# FPGA_B.net
KiCad netlist of a schematic drawn in Altium Designer
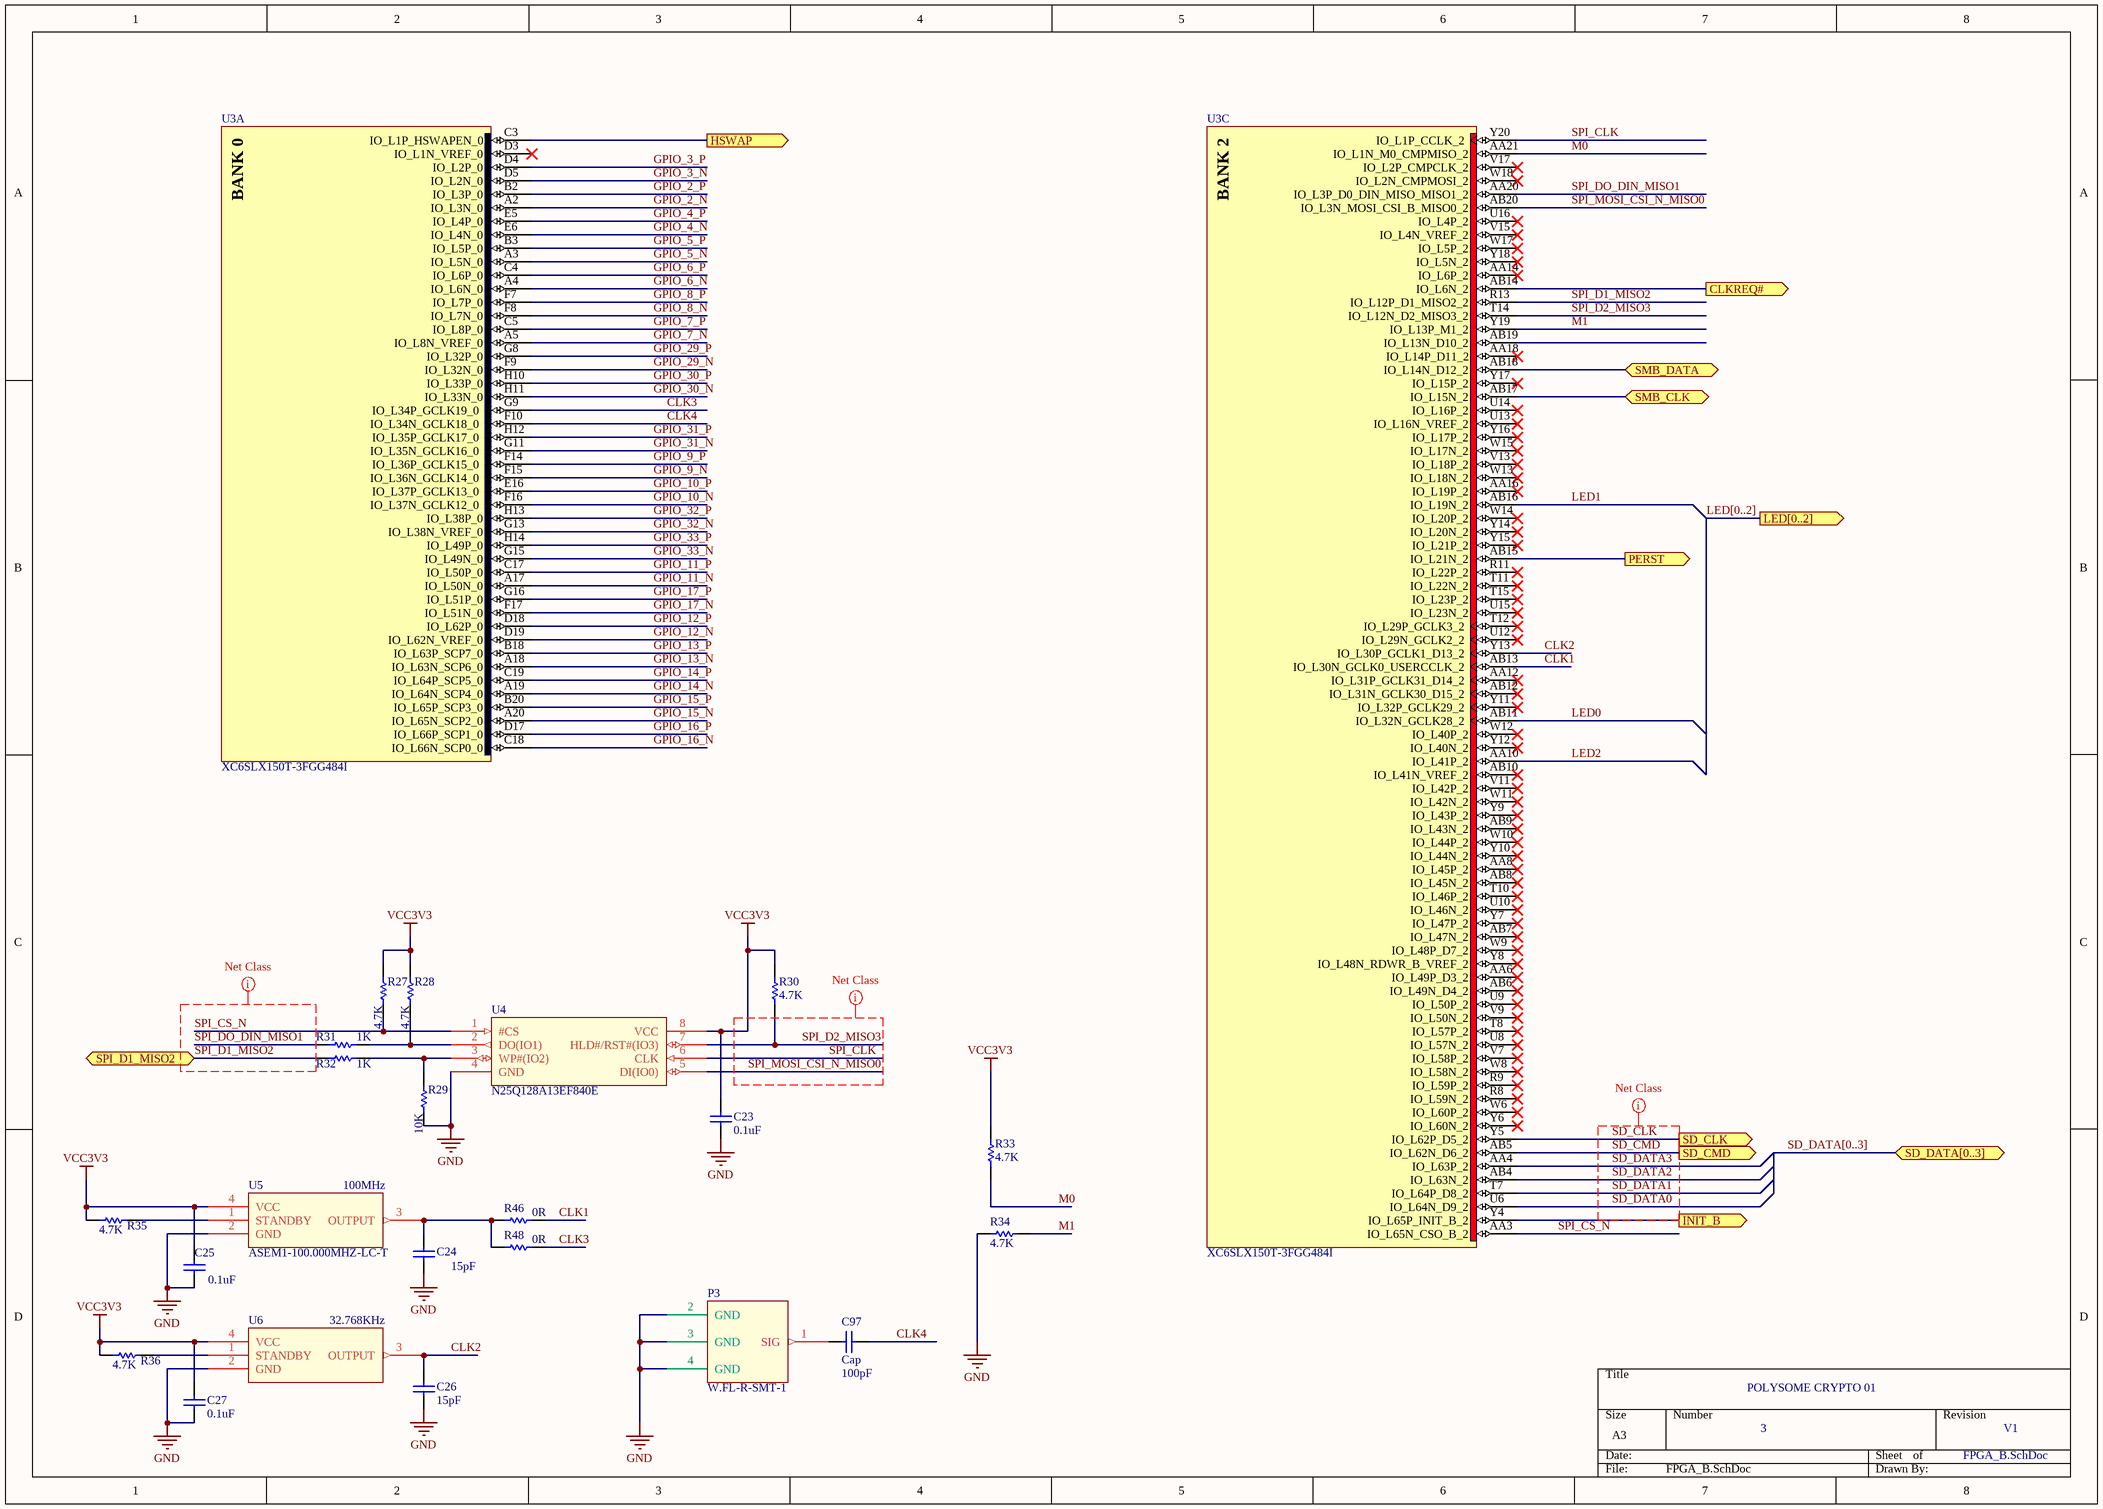
[diagram p0: FPGA_B.SchDoc]

(export (version "E")
  (design (tool "Eeschema 10.0.6"))
  (components
    (comp (ref "C23")
      (value "0.1uF")
      (footprint "0402")
      (description "Capacitor (Semiconductor SIM Model)")
      (fields (field (name "Comment") "Cap Semi") (field (name "PUBLISHER") "Altium Limited"))
      (libsource (lib "Miscellaneous Devices") (part "Cap Semi"))
    )
    (comp (ref "C24")
      (value "15pF")
      (footprint "0402")
      (description "Capacitor (Semiconductor SIM Model)")
      (fields (field (name "Comment") "Cap Semi") (field (name "PUBLISHER") "Altium Limited"))
      (libsource (lib "Miscellaneous Devices") (part "Cap Semi"))
    )
    (comp (ref "C25")
      (value "0.1uF")
      (footprint "0402")
      (description "Capacitor (Semiconductor SIM Model)")
      (fields (field (name "Comment") "Cap Semi") (field (name "PUBLISHER") "Altium Limited"))
      (libsource (lib "Miscellaneous Devices") (part "Cap Semi"))
    )
    (comp (ref "C26")
      (value "15pF")
      (footprint "0402")
      (description "Capacitor (Semiconductor SIM Model)")
      (fields (field (name "Comment") "Cap Semi") (field (name "PUBLISHER") "Altium Limited"))
      (libsource (lib "Miscellaneous Devices") (part "Cap Semi"))
    )
    (comp (ref "C27")
      (value "0.1uF")
      (footprint "0402")
      (description "Capacitor (Semiconductor SIM Model)")
      (fields (field (name "Comment") "Cap Semi") (field (name "PUBLISHER") "Altium Limited"))
      (libsource (lib "Miscellaneous Devices") (part "Cap Semi"))
    )
    (comp (ref "C97")
      (value "Cap")
      (footprint "0402")
      (description "Capacitor")
      (fields (field (name "ALTIUM_VALUE") "100pF") (field (name "PUBLISHER") "Altium Limited"))
      (libsource (lib "Miscellaneous Devices") (part "Cap"))
    )
    (comp (ref "P3")
      (value "W.FL-R-SMT-1")
      (footprint "W.FL-R-SMT-1")
      (libsource (lib "PolySomeCrypto01") (part "W.FL-R-SMT-1"))
    )
    (comp (ref "R27")
      (value "4.7K")
      (footprint "0402")
      (description "Semiconductor Resistor")
      (fields (field (name "Comment") "Res Semi") (field (name "PUBLISHER") "Altium Limited"))
      (libsource (lib "Miscellaneous Devices") (part "Res Semi"))
    )
    (comp (ref "R28")
      (value "4.7K")
      (footprint "0402")
      (description "Semiconductor Resistor")
      (fields (field (name "Comment") "Res Semi") (field (name "PUBLISHER") "Altium Limited"))
      (libsource (lib "Miscellaneous Devices") (part "Res Semi"))
    )
    (comp (ref "R29")
      (value "10K")
      (footprint "0402")
      (description "Semiconductor Resistor")
      (fields (field (name "Comment") "Res Semi") (field (name "PUBLISHER") "Altium Limited"))
      (libsource (lib "Miscellaneous Devices") (part "Res Semi"))
    )
    (comp (ref "R30")
      (value "4.7K")
      (footprint "0402")
      (description "Semiconductor Resistor")
      (fields (field (name "Comment") "Res Semi") (field (name "PUBLISHER") "Altium Limited"))
      (libsource (lib "Miscellaneous Devices") (part "Res Semi"))
    )
    (comp (ref "R31")
      (value "1K")
      (footprint "0402")
      (description "Semiconductor Resistor")
      (fields (field (name "Comment") "Res Semi") (field (name "PUBLISHER") "Altium Limited"))
      (libsource (lib "Miscellaneous Devices") (part "Res Semi"))
    )
    (comp (ref "R32")
      (value "1K")
      (footprint "0402")
      (description "Semiconductor Resistor")
      (fields (field (name "Comment") "Res Semi") (field (name "PUBLISHER") "Altium Limited"))
      (libsource (lib "Miscellaneous Devices") (part "Res Semi"))
    )
    (comp (ref "R33")
      (value "4.7K")
      (footprint "0402")
      (description "Semiconductor Resistor")
      (fields (field (name "Comment") "Res Semi") (field (name "PUBLISHER") "Altium Limited"))
      (libsource (lib "Miscellaneous Devices") (part "Res Semi"))
    )
    (comp (ref "R34")
      (value "4.7K")
      (footprint "0402")
      (description "Semiconductor Resistor")
      (fields (field (name "Comment") "Res Semi") (field (name "PUBLISHER") "Altium Limited"))
      (libsource (lib "Miscellaneous Devices") (part "Res Semi"))
    )
    (comp (ref "R35")
      (value "4.7K")
      (footprint "0402")
      (description "Semiconductor Resistor")
      (fields (field (name "Comment") "Res Semi") (field (name "PUBLISHER") "Altium Limited"))
      (libsource (lib "Miscellaneous Devices") (part "Res Semi"))
    )
    (comp (ref "R36")
      (value "4.7K")
      (footprint "0402")
      (description "Semiconductor Resistor")
      (fields (field (name "Comment") "Res Semi") (field (name "PUBLISHER") "Altium Limited"))
      (libsource (lib "Miscellaneous Devices") (part "Res Semi"))
    )
    (comp (ref "R46")
      (value "0R")
      (footprint "0402")
      (description "Semiconductor Resistor")
      (fields (field (name "Comment") "Res Semi") (field (name "PUBLISHER") "Altium Limited"))
      (libsource (lib "Miscellaneous Devices") (part "Res Semi"))
    )
    (comp (ref "R48")
      (value "0R")
      (footprint "0402")
      (description "Semiconductor Resistor")
      (fields (field (name "Comment") "Res Semi") (field (name "PUBLISHER") "Altium Limited"))
      (libsource (lib "Miscellaneous Devices") (part "Res Semi"))
    )
    (comp (ref "U3")
      (value "XC6SLX150T-3FGG484I")
      (footprint "FGG484")
      (fields (field (name "PUBLISHER") "Altium Limited"))
      (libsource (lib "Xilinx Spartan-6") (part "XC6SLX150T-3FGG484I"))
    )
    (comp (ref "U4")
      (value "N25Q128A13EF840E")
      (footprint "8S2_L")
      (description "IC FLASH 128MBIT 108MHZ 8VDFN")
      (fields (field (name "MANUFACTURER") "Micron Technology Inc"))
      (libsource (lib "PolySomeCrypto01") (part "N25Q128A13EF840E"))
    )
    (comp (ref "U5")
      (value "ASEM1-100.000MHZ-LC-T")
      (footprint "DFN170P200X100-4N")
      (description "ABRACON - ASEM1-100.000MHZ-LC-T - MEMS OSC, 100MHZ, 3.2 X 2.5MM, CMOS")
      (fields (field (name "MANUFACTURER") "ABRACON"))
      (libsource (lib "PolySomeCrypto01") (part "ASEM1-100.000MHZ-LC-T"))
    )
    (comp (ref "U6")
      (value "ASEM1-LC-T")
      (description "ABRACON - ASEM1-HZ-LC-T - MEMS OSC, 3.2 X 2.5MM, CMOS")
      (fields
        (field (name "MANUFACTURER") "ABRACON")
        (field (name "MANUFACTURER PART NUMBER") "ASEM1-xxxxMHZ-LC-T")
      )
      (libsource (lib "PolySomeCrypto01") (part "ASEM1-HZ-LC-T"))
    )
  )
  (nets
    (net (code "1") (name "/CLK1") (class "Default")
      (node (ref "R46") (pin "2") (pinfunction "2_2") (pintype "passive"))
      (node (ref "U3") (pin "AB13") (pinfunction "IO_L30N_GCLK0_USERCCLK_2_AB13") (pintype "bidirectional"))
    )
    (net (code "2") (name "/CLK2") (class "Default")
      (node (ref "C26") (pin "1") (pinfunction "1_1") (pintype "passive"))
      (node (ref "U3") (pin "Y13") (pinfunction "IO_L30P_GCLK1_D13_2_Y13") (pintype "bidirectional"))
      (node (ref "U6") (pin "3") (pinfunction "OUTPUT_3") (pintype "output"))
    )
    (net (code "3") (name "/CLK3") (class "Default")
      (node (ref "R48") (pin "2") (pinfunction "2_2") (pintype "passive"))
      (node (ref "U3") (pin "G9") (pinfunction "IO_L34P_GCLK19_0_G9") (pintype "bidirectional"))
    )
    (net (code "4") (name "/CLK4") (class "Default")
      (node (ref "C97") (pin "2") (pinfunction "2_2") (pintype "passive"))
      (node (ref "U3") (pin "F10") (pinfunction "IO_L34N_GCLK18_0_F10") (pintype "bidirectional"))
    )
    (net (code "5") (name "/CLKREQ#") (class "Default")
      (node (ref "U3") (pin "AB14") (pinfunction "IO_L6N_2_AB14") (pintype "bidirectional"))
    )
    (net (code "6") (name "/GPIO_2_N") (class "Default")
      (node (ref "U3") (pin "A2") (pinfunction "IO_L3N_0_A2") (pintype "bidirectional"))
    )
    (net (code "7") (name "/GPIO_2_P") (class "Default")
      (node (ref "U3") (pin "B2") (pinfunction "IO_L3P_0_B2") (pintype "bidirectional"))
    )
    (net (code "8") (name "/GPIO_3_N") (class "Default")
      (node (ref "U3") (pin "D5") (pinfunction "IO_L2N_0_D5") (pintype "bidirectional"))
    )
    (net (code "9") (name "/GPIO_3_P") (class "Default")
      (node (ref "U3") (pin "D4") (pinfunction "IO_L2P_0_D4") (pintype "bidirectional"))
    )
    (net (code "10") (name "/GPIO_4_N") (class "Default")
      (node (ref "U3") (pin "E6") (pinfunction "IO_L4N_0_E6") (pintype "bidirectional"))
    )
    (net (code "11") (name "/GPIO_4_P") (class "Default")
      (node (ref "U3") (pin "E5") (pinfunction "IO_L4P_0_E5") (pintype "bidirectional"))
    )
    (net (code "12") (name "/GPIO_5_N") (class "Default")
      (node (ref "U3") (pin "A3") (pinfunction "IO_L5N_0_A3") (pintype "bidirectional"))
    )
    (net (code "13") (name "/GPIO_5_P") (class "Default")
      (node (ref "U3") (pin "B3") (pinfunction "IO_L5P_0_B3") (pintype "bidirectional"))
    )
    (net (code "14") (name "/GPIO_6_N") (class "Default")
      (node (ref "U3") (pin "A4") (pinfunction "IO_L6N_0_A4") (pintype "bidirectional"))
    )
    (net (code "15") (name "/GPIO_6_P") (class "Default")
      (node (ref "U3") (pin "C4") (pinfunction "IO_L6P_0_C4") (pintype "bidirectional"))
    )
    (net (code "16") (name "/GPIO_7_N") (class "Default")
      (node (ref "U3") (pin "A5") (pinfunction "IO_L8N_VREF_0_A5") (pintype "bidirectional"))
    )
    (net (code "17") (name "/GPIO_7_P") (class "Default")
      (node (ref "U3") (pin "C5") (pinfunction "IO_L8P_0_C5") (pintype "bidirectional"))
    )
    (net (code "18") (name "/GPIO_8_N") (class "Default")
      (node (ref "U3") (pin "F8") (pinfunction "IO_L7N_0_F8") (pintype "bidirectional"))
    )
    (net (code "19") (name "/GPIO_8_P") (class "Default")
      (node (ref "U3") (pin "F7") (pinfunction "IO_L7P_0_F7") (pintype "bidirectional"))
    )
    (net (code "20") (name "/GPIO_9_N") (class "Default")
      (node (ref "U3") (pin "F15") (pinfunction "IO_L36N_GCLK14_0_F15") (pintype "bidirectional"))
    )
    (net (code "21") (name "/GPIO_9_P") (class "Default")
      (node (ref "U3") (pin "F14") (pinfunction "IO_L36P_GCLK15_0_F14") (pintype "bidirectional"))
    )
    (net (code "22") (name "/GPIO_10_N") (class "Default")
      (node (ref "U3") (pin "F16") (pinfunction "IO_L37N_GCLK12_0_F16") (pintype "bidirectional"))
    )
    (net (code "23") (name "/GPIO_10_P") (class "Default")
      (node (ref "U3") (pin "E16") (pinfunction "IO_L37P_GCLK13_0_E16") (pintype "bidirectional"))
    )
    (net (code "24") (name "/GPIO_11_N") (class "Default")
      (node (ref "U3") (pin "A17") (pinfunction "IO_L50N_0_A17") (pintype "bidirectional"))
    )
    (net (code "25") (name "/GPIO_11_P") (class "Default")
      (node (ref "U3") (pin "C17") (pinfunction "IO_L50P_0_C17") (pintype "bidirectional"))
    )
    (net (code "26") (name "/GPIO_12_N") (class "Default")
      (node (ref "U3") (pin "D19") (pinfunction "IO_L62N_VREF_0_D19") (pintype "bidirectional"))
    )
    (net (code "27") (name "/GPIO_12_P") (class "Default")
      (node (ref "U3") (pin "D18") (pinfunction "IO_L62P_0_D18") (pintype "bidirectional"))
    )
    (net (code "28") (name "/GPIO_13_N") (class "Default")
      (node (ref "U3") (pin "A18") (pinfunction "IO_L63N_SCP6_0_A18") (pintype "bidirectional"))
    )
    (net (code "29") (name "/GPIO_13_P") (class "Default")
      (node (ref "U3") (pin "B18") (pinfunction "IO_L63P_SCP7_0_B18") (pintype "bidirectional"))
    )
    (net (code "30") (name "/GPIO_14_N") (class "Default")
      (node (ref "U3") (pin "A19") (pinfunction "IO_L64N_SCP4_0_A19") (pintype "bidirectional"))
    )
    (net (code "31") (name "/GPIO_14_P") (class "Default")
      (node (ref "U3") (pin "C19") (pinfunction "IO_L64P_SCP5_0_C19") (pintype "bidirectional"))
    )
    (net (code "32") (name "/GPIO_15_N") (class "Default")
      (node (ref "U3") (pin "A20") (pinfunction "IO_L65N_SCP2_0_A20") (pintype "bidirectional"))
    )
    (net (code "33") (name "/GPIO_15_P") (class "Default")
      (node (ref "U3") (pin "B20") (pinfunction "IO_L65P_SCP3_0_B20") (pintype "bidirectional"))
    )
    (net (code "34") (name "/GPIO_16_N") (class "Default")
      (node (ref "U3") (pin "C18") (pinfunction "IO_L66N_SCP0_0_C18") (pintype "bidirectional"))
    )
    (net (code "35") (name "/GPIO_16_P") (class "Default")
      (node (ref "U3") (pin "D17") (pinfunction "IO_L66P_SCP1_0_D17") (pintype "bidirectional"))
    )
    (net (code "36") (name "/GPIO_17_N") (class "Default")
      (node (ref "U3") (pin "F17") (pinfunction "IO_L51N_0_F17") (pintype "bidirectional"))
    )
    (net (code "37") (name "/GPIO_17_P") (class "Default")
      (node (ref "U3") (pin "G16") (pinfunction "IO_L51P_0_G16") (pintype "bidirectional"))
    )
    (net (code "38") (name "/GPIO_29_N") (class "Default")
      (node (ref "U3") (pin "F9") (pinfunction "IO_L32N_0_F9") (pintype "bidirectional"))
    )
    (net (code "39") (name "/GPIO_29_P") (class "Default")
      (node (ref "U3") (pin "G8") (pinfunction "IO_L32P_0_G8") (pintype "bidirectional"))
    )
    (net (code "40") (name "/GPIO_30_N") (class "Default")
      (node (ref "U3") (pin "H11") (pinfunction "IO_L33N_0_H11") (pintype "bidirectional"))
    )
    (net (code "41") (name "/GPIO_30_P") (class "Default")
      (node (ref "U3") (pin "H10") (pinfunction "IO_L33P_0_H10") (pintype "bidirectional"))
    )
    (net (code "42") (name "/GPIO_31_N") (class "Default")
      (node (ref "U3") (pin "G11") (pinfunction "IO_L35N_GCLK16_0_G11") (pintype "bidirectional"))
    )
    (net (code "43") (name "/GPIO_31_P") (class "Default")
      (node (ref "U3") (pin "H12") (pinfunction "IO_L35P_GCLK17_0_H12") (pintype "bidirectional"))
    )
    (net (code "44") (name "/GPIO_32_N") (class "Default")
      (node (ref "U3") (pin "G13") (pinfunction "IO_L38N_VREF_0_G13") (pintype "bidirectional"))
    )
    (net (code "45") (name "/GPIO_32_P") (class "Default")
      (node (ref "U3") (pin "H13") (pinfunction "IO_L38P_0_H13") (pintype "bidirectional"))
    )
    (net (code "46") (name "/GPIO_33_N") (class "Default")
      (node (ref "U3") (pin "G15") (pinfunction "IO_L49N_0_G15") (pintype "bidirectional"))
    )
    (net (code "47") (name "/GPIO_33_P") (class "Default")
      (node (ref "U3") (pin "H14") (pinfunction "IO_L49P_0_H14") (pintype "bidirectional"))
    )
    (net (code "48") (name "/HSWAP") (class "Default")
      (node (ref "U3") (pin "C3") (pinfunction "IO_L1P_HSWAPEN_0_C3") (pintype "bidirectional"))
    )
    (net (code "49") (name "/INIT_B") (class "Default")
      (node (ref "U3") (pin "Y4") (pinfunction "IO_L65P_INIT_B_2_Y4") (pintype "bidirectional"))
    )
    (net (code "50") (name "/LED0") (class "Default")
      (node (ref "U3") (pin "AB11") (pinfunction "IO_L32N_GCLK28_2_AB11") (pintype "bidirectional"))
    )
    (net (code "51") (name "/LED1") (class "Default")
      (node (ref "U3") (pin "AB16") (pinfunction "IO_L19N_2_AB16") (pintype "bidirectional"))
    )
    (net (code "52") (name "/LED2") (class "Default")
      (node (ref "U3") (pin "AA10") (pinfunction "IO_L41P_2_AA10") (pintype "bidirectional"))
    )
    (net (code "54") (name "/M0") (class "Default")
      (node (ref "R33") (pin "1") (pinfunction "1_1") (pintype "passive"))
      (node (ref "U3") (pin "AA21") (pinfunction "IO_L1N_M0_CMPMISO_2_AA21") (pintype "bidirectional"))
    )
    (net (code "55") (name "/M1") (class "Default")
      (node (ref "R34") (pin "1") (pinfunction "1_1") (pintype "passive"))
      (node (ref "U3") (pin "Y19") (pinfunction "IO_L13P_M1_2_Y19") (pintype "bidirectional"))
    )
    (net (code "56") (name "/PERST") (class "Default")
      (node (ref "U3") (pin "AB15") (pinfunction "IO_L21N_2_AB15") (pintype "bidirectional"))
    )
    (net (code "57") (name "/SD_CLK") (class "Default")
      (node (ref "U3") (pin "Y5") (pinfunction "IO_L62P_D5_2_Y5") (pintype "bidirectional"))
    )
    (net (code "58") (name "/SD_CMD") (class "Default")
      (node (ref "U3") (pin "AB5") (pinfunction "IO_L62N_D6_2_AB5") (pintype "bidirectional"))
    )
    (net (code "59") (name "/SD_DATA0") (class "Default")
      (node (ref "U3") (pin "U6") (pinfunction "IO_L64N_D9_2_U6") (pintype "bidirectional"))
    )
    (net (code "60") (name "/SD_DATA1") (class "Default")
      (node (ref "U3") (pin "T7") (pinfunction "IO_L64P_D8_2_T7") (pintype "bidirectional"))
    )
    (net (code "61") (name "/SD_DATA2") (class "Default")
      (node (ref "U3") (pin "AB4") (pinfunction "IO_L63N_2_AB4") (pintype "bidirectional"))
    )
    (net (code "62") (name "/SD_DATA3") (class "Default")
      (node (ref "U3") (pin "AA4") (pinfunction "IO_L63P_2_AA4") (pintype "bidirectional"))
    )
    (net (code "64") (name "/SMB_CLK") (class "Default")
      (node (ref "U3") (pin "AB17") (pinfunction "IO_L15N_2_AB17") (pintype "bidirectional"))
    )
    (net (code "65") (name "/SMB_DATA") (class "Default")
      (node (ref "U3") (pin "AB18") (pinfunction "IO_L14N_D12_2_AB18") (pintype "bidirectional"))
    )
    (net (code "66") (name "/SPI_CLK") (class "Default")
      (node (ref "U3") (pin "Y20") (pinfunction "IO_L1P_CCLK_2_Y20") (pintype "bidirectional"))
      (node (ref "U4") (pin "6") (pinfunction "CLK_6") (pintype "input"))
    )
    (net (code "67") (name "/SPI_CS_N") (class "Default")
      (node (ref "R27") (pin "1") (pinfunction "1_1") (pintype "passive"))
      (node (ref "U3") (pin "AA3") (pinfunction "IO_L65N_CSO_B_2_AA3") (pintype "bidirectional"))
      (node (ref "U4") (pin "1") (pinfunction "#CS_1") (pintype "input"))
    )
    (net (code "68") (name "/SPI_D1_MISO2") (class "Default")
      (node (ref "R32") (pin "1") (pinfunction "1_1") (pintype "passive"))
      (node (ref "U3") (pin "R13") (pinfunction "IO_L12P_D1_MISO2_2_R13") (pintype "bidirectional"))
    )
    (net (code "69") (name "/SPI_D2_MISO3") (class "Default")
      (node (ref "R30") (pin "1") (pinfunction "1_1") (pintype "passive"))
      (node (ref "U3") (pin "T14") (pinfunction "IO_L12N_D2_MISO3_2_T14") (pintype "bidirectional"))
      (node (ref "U4") (pin "7") (pinfunction "HLD#/RST#(IO3)_7") (pintype "bidirectional"))
    )
    (net (code "70") (name "/SPI_DO_DIN_MISO1") (class "Default")
      (node (ref "R31") (pin "1") (pinfunction "1_1") (pintype "passive"))
      (node (ref "U3") (pin "AA20") (pinfunction "IO_L3P_D0_DIN_MISO_MISO1_2_AA20") (pintype "bidirectional"))
    )
    (net (code "71") (name "/SPI_MOSI_CSI_N_MISO0") (class "Default")
      (node (ref "U3") (pin "AB20") (pinfunction "IO_L3N_MOSI_CSI_B_MISO0_2_AB20") (pintype "bidirectional"))
      (node (ref "U4") (pin "5") (pinfunction "DI(IO0)_5") (pintype "bidirectional"))
    )
    (net (code "72") (name "GND") (class "Default")
      (node (ref "C23") (pin "1") (pinfunction "1_1") (pintype "passive"))
      (node (ref "C24") (pin "1") (pinfunction "1_1") (pintype "passive"))
      (node (ref "C25") (pin "2") (pinfunction "2_2") (pintype "passive"))
      (node (ref "C26") (pin "2") (pinfunction "2_2") (pintype "passive"))
      (node (ref "C27") (pin "2") (pinfunction "2_2") (pintype "passive"))
      (node (ref "P3") (pin "2") (pinfunction "GND_2") (pintype "passive"))
      (node (ref "P3") (pin "3") (pinfunction "GND_3") (pintype "passive"))
      (node (ref "P3") (pin "4") (pinfunction "GND_4") (pintype "passive"))
      (node (ref "R29") (pin "1") (pinfunction "1_1") (pintype "passive"))
      (node (ref "R34") (pin "2") (pinfunction "2_2") (pintype "passive"))
      (node (ref "U4") (pin "4") (pinfunction "GND_4") (pintype "power_in"))
      (node (ref "U5") (pin "2") (pinfunction "GND_2") (pintype "power_in"))
      (node (ref "U6") (pin "2") (pinfunction "GND_2") (pintype "power_in"))
    )
    (net (code "73") (name "Net-(P3-SIG)") (class "Default")
      (node (ref "C97") (pin "1") (pinfunction "1_1") (pintype "passive"))
      (node (ref "P3") (pin "1") (pinfunction "SIG_1") (pintype "output"))
    )
    (net (code "74") (name "Net-(U4-DO(IO1))") (class "Default")
      (node (ref "R28") (pin "1") (pinfunction "1_1") (pintype "passive"))
      (node (ref "R31") (pin "2") (pinfunction "2_2") (pintype "passive"))
      (node (ref "U4") (pin "2") (pinfunction "DO(IO1)_2") (pintype "output"))
    )
    (net (code "75") (name "Net-(U4-WP#(IO2))") (class "Default")
      (node (ref "R29") (pin "2") (pinfunction "2_2") (pintype "passive"))
      (node (ref "R32") (pin "2") (pinfunction "2_2") (pintype "passive"))
      (node (ref "U4") (pin "3") (pinfunction "WP#(IO2)_3") (pintype "bidirectional"))
    )
    (net (code "76") (name "Net-(U5-OUTPUT)") (class "Default")
      (node (ref "C24") (pin "2") (pinfunction "2_2") (pintype "passive"))
      (node (ref "R46") (pin "1") (pinfunction "1_1") (pintype "passive"))
      (node (ref "R48") (pin "1") (pinfunction "1_1") (pintype "passive"))
      (node (ref "U5") (pin "3") (pinfunction "OUTPUT_3") (pintype "output"))
    )
    (net (code "77") (name "Net-(U5-STANDBY)") (class "Default")
      (node (ref "R35") (pin "2") (pinfunction "2_2") (pintype "passive"))
      (node (ref "U5") (pin "1") (pinfunction "STANDBY_1") (pintype "power_in"))
    )
    (net (code "78") (name "Net-(U6-STANDBY)") (class "Default")
      (node (ref "R36") (pin "2") (pinfunction "2_2") (pintype "passive"))
      (node (ref "U6") (pin "1") (pinfunction "STANDBY_1") (pintype "power_in"))
    )
    (net (code "79") (name "VCC3V3") (class "Default")
      (node (ref "C23") (pin "2") (pinfunction "2_2") (pintype "passive"))
      (node (ref "C25") (pin "1") (pinfunction "1_1") (pintype "passive"))
      (node (ref "C27") (pin "1") (pinfunction "1_1") (pintype "passive"))
      (node (ref "R27") (pin "2") (pinfunction "2_2") (pintype "passive"))
      (node (ref "R28") (pin "2") (pinfunction "2_2") (pintype "passive"))
      (node (ref "R30") (pin "2") (pinfunction "2_2") (pintype "passive"))
      (node (ref "R33") (pin "2") (pinfunction "2_2") (pintype "passive"))
      (node (ref "R35") (pin "1") (pinfunction "1_1") (pintype "passive"))
      (node (ref "R36") (pin "1") (pinfunction "1_1") (pintype "passive"))
      (node (ref "U4") (pin "8") (pinfunction "VCC_8") (pintype "power_in"))
      (node (ref "U5") (pin "4") (pinfunction "VCC_4") (pintype "power_in"))
      (node (ref "U6") (pin "4") (pinfunction "VCC_4") (pintype "power_in"))
    )
    (net (code "80") (name "unconnected-(U3A-IO_L1N_VREF_0-PadD3)") (class "Default")
      (node (ref "U3") (pin "D3") (pinfunction "IO_L1N_VREF_0_D3") (pintype "bidirectional+no_connect"))
    )
    (net (code "81") (name "unconnected-(U3C-IO_L2N_CMPMOSI_2-PadW18)") (class "Default")
      (node (ref "U3") (pin "W18") (pinfunction "IO_L2N_CMPMOSI_2_W18") (pintype "bidirectional+no_connect"))
    )
    (net (code "82") (name "unconnected-(U3C-IO_L2P_CMPCLK_2-PadV17)") (class "Default")
      (node (ref "U3") (pin "V17") (pinfunction "IO_L2P_CMPCLK_2_V17") (pintype "bidirectional+no_connect"))
    )
    (net (code "83") (name "unconnected-(U3C-IO_L4N_VREF_2-PadV15)") (class "Default")
      (node (ref "U3") (pin "V15") (pinfunction "IO_L4N_VREF_2_V15") (pintype "bidirectional+no_connect"))
    )
    (net (code "84") (name "unconnected-(U3C-IO_L4P_2-PadU16)") (class "Default")
      (node (ref "U3") (pin "U16") (pinfunction "IO_L4P_2_U16") (pintype "bidirectional+no_connect"))
    )
    (net (code "85") (name "unconnected-(U3C-IO_L5N_2-PadY18)") (class "Default")
      (node (ref "U3") (pin "Y18") (pinfunction "IO_L5N_2_Y18") (pintype "bidirectional+no_connect"))
    )
    (net (code "86") (name "unconnected-(U3C-IO_L5P_2-PadW17)") (class "Default")
      (node (ref "U3") (pin "W17") (pinfunction "IO_L5P_2_W17") (pintype "bidirectional+no_connect"))
    )
    (net (code "87") (name "unconnected-(U3C-IO_L6P_2-PadAA14)") (class "Default")
      (node (ref "U3") (pin "AA14") (pinfunction "IO_L6P_2_AA14") (pintype "bidirectional+no_connect"))
    )
    (net (code "88") (name "unconnected-(U3C-IO_L13N_D10_2-PadAB19)") (class "Default")
      (node (ref "U3") (pin "AB19") (pinfunction "IO_L13N_D10_2_AB19") (pintype "bidirectional"))
    )
    (net (code "89") (name "unconnected-(U3C-IO_L14P_D11_2-PadAA18)") (class "Default")
      (node (ref "U3") (pin "AA18") (pinfunction "IO_L14P_D11_2_AA18") (pintype "bidirectional+no_connect"))
    )
    (net (code "90") (name "unconnected-(U3C-IO_L15P_2-PadY17)") (class "Default")
      (node (ref "U3") (pin "Y17") (pinfunction "IO_L15P_2_Y17") (pintype "bidirectional+no_connect"))
    )
    (net (code "91") (name "unconnected-(U3C-IO_L16N_VREF_2-PadU13)") (class "Default")
      (node (ref "U3") (pin "U13") (pinfunction "IO_L16N_VREF_2_U13") (pintype "bidirectional+no_connect"))
    )
    (net (code "92") (name "unconnected-(U3C-IO_L16P_2-PadU14)") (class "Default")
      (node (ref "U3") (pin "U14") (pinfunction "IO_L16P_2_U14") (pintype "bidirectional+no_connect"))
    )
    (net (code "93") (name "unconnected-(U3C-IO_L17N_2-PadW15)") (class "Default")
      (node (ref "U3") (pin "W15") (pinfunction "IO_L17N_2_W15") (pintype "bidirectional+no_connect"))
    )
    (net (code "94") (name "unconnected-(U3C-IO_L17P_2-PadY16)") (class "Default")
      (node (ref "U3") (pin "Y16") (pinfunction "IO_L17P_2_Y16") (pintype "bidirectional+no_connect"))
    )
    (net (code "95") (name "unconnected-(U3C-IO_L18N_2-PadW13)") (class "Default")
      (node (ref "U3") (pin "W13") (pinfunction "IO_L18N_2_W13") (pintype "bidirectional+no_connect"))
    )
    (net (code "96") (name "unconnected-(U3C-IO_L18P_2-PadV13)") (class "Default")
      (node (ref "U3") (pin "V13") (pinfunction "IO_L18P_2_V13") (pintype "bidirectional+no_connect"))
    )
    (net (code "97") (name "unconnected-(U3C-IO_L19P_2-PadAA16)") (class "Default")
      (node (ref "U3") (pin "AA16") (pinfunction "IO_L19P_2_AA16") (pintype "bidirectional+no_connect"))
    )
    (net (code "98") (name "unconnected-(U3C-IO_L20N_2-PadY14)") (class "Default")
      (node (ref "U3") (pin "Y14") (pinfunction "IO_L20N_2_Y14") (pintype "bidirectional+no_connect"))
    )
    (net (code "99") (name "unconnected-(U3C-IO_L20P_2-PadW14)") (class "Default")
      (node (ref "U3") (pin "W14") (pinfunction "IO_L20P_2_W14") (pintype "bidirectional+no_connect"))
    )
    (net (code "100") (name "unconnected-(U3C-IO_L21P_2-PadY15)") (class "Default")
      (node (ref "U3") (pin "Y15") (pinfunction "IO_L21P_2_Y15") (pintype "bidirectional+no_connect"))
    )
    (net (code "101") (name "unconnected-(U3C-IO_L22N_2-PadT11)") (class "Default")
      (node (ref "U3") (pin "T11") (pinfunction "IO_L22N_2_T11") (pintype "bidirectional+no_connect"))
    )
    (net (code "102") (name "unconnected-(U3C-IO_L22P_2-PadR11)") (class "Default")
      (node (ref "U3") (pin "R11") (pinfunction "IO_L22P_2_R11") (pintype "bidirectional+no_connect"))
    )
    (net (code "103") (name "unconnected-(U3C-IO_L23N_2-PadU15)") (class "Default")
      (node (ref "U3") (pin "U15") (pinfunction "IO_L23N_2_U15") (pintype "bidirectional+no_connect"))
    )
    (net (code "104") (name "unconnected-(U3C-IO_L23P_2-PadT15)") (class "Default")
      (node (ref "U3") (pin "T15") (pinfunction "IO_L23P_2_T15") (pintype "bidirectional+no_connect"))
    )
    (net (code "105") (name "unconnected-(U3C-IO_L29N_GCLK2_2-PadU12)") (class "Default")
      (node (ref "U3") (pin "U12") (pinfunction "IO_L29N_GCLK2_2_U12") (pintype "bidirectional+no_connect"))
    )
    (net (code "106") (name "unconnected-(U3C-IO_L29P_GCLK3_2-PadT12)") (class "Default")
      (node (ref "U3") (pin "T12") (pinfunction "IO_L29P_GCLK3_2_T12") (pintype "bidirectional+no_connect"))
    )
    (net (code "107") (name "unconnected-(U3C-IO_L31N_GCLK30_D15_2-PadAB12)") (class "Default")
      (node (ref "U3") (pin "AB12") (pinfunction "IO_L31N_GCLK30_D15_2_AB12") (pintype "bidirectional+no_connect"))
    )
    (net (code "108") (name "unconnected-(U3C-IO_L31P_GCLK31_D14_2-PadAA12)") (class "Default")
      (node (ref "U3") (pin "AA12") (pinfunction "IO_L31P_GCLK31_D14_2_AA12") (pintype "bidirectional+no_connect"))
    )
    (net (code "109") (name "unconnected-(U3C-IO_L32P_GCLK29_2-PadY11)") (class "Default")
      (node (ref "U3") (pin "Y11") (pinfunction "IO_L32P_GCLK29_2_Y11") (pintype "bidirectional+no_connect"))
    )
    (net (code "110") (name "unconnected-(U3C-IO_L40N_2-PadY12)") (class "Default")
      (node (ref "U3") (pin "Y12") (pinfunction "IO_L40N_2_Y12") (pintype "bidirectional+no_connect"))
    )
    (net (code "111") (name "unconnected-(U3C-IO_L40P_2-PadW12)") (class "Default")
      (node (ref "U3") (pin "W12") (pinfunction "IO_L40P_2_W12") (pintype "bidirectional+no_connect"))
    )
    (net (code "112") (name "unconnected-(U3C-IO_L41N_VREF_2-PadAB10)") (class "Default")
      (node (ref "U3") (pin "AB10") (pinfunction "IO_L41N_VREF_2_AB10") (pintype "bidirectional+no_connect"))
    )
    (net (code "113") (name "unconnected-(U3C-IO_L42N_2-PadW11)") (class "Default")
      (node (ref "U3") (pin "W11") (pinfunction "IO_L42N_2_W11") (pintype "bidirectional+no_connect"))
    )
    (net (code "114") (name "unconnected-(U3C-IO_L42P_2-PadV11)") (class "Default")
      (node (ref "U3") (pin "V11") (pinfunction "IO_L42P_2_V11") (pintype "bidirectional+no_connect"))
    )
    (net (code "115") (name "unconnected-(U3C-IO_L43N_2-PadAB9)") (class "Default")
      (node (ref "U3") (pin "AB9") (pinfunction "IO_L43N_2_AB9") (pintype "bidirectional+no_connect"))
    )
    (net (code "116") (name "unconnected-(U3C-IO_L43P_2-PadY9)") (class "Default")
      (node (ref "U3") (pin "Y9") (pinfunction "IO_L43P_2_Y9") (pintype "bidirectional+no_connect"))
    )
    (net (code "117") (name "unconnected-(U3C-IO_L44N_2-PadY10)") (class "Default")
      (node (ref "U3") (pin "Y10") (pinfunction "IO_L44N_2_Y10") (pintype "bidirectional+no_connect"))
    )
    (net (code "118") (name "unconnected-(U3C-IO_L44P_2-PadW10)") (class "Default")
      (node (ref "U3") (pin "W10") (pinfunction "IO_L44P_2_W10") (pintype "bidirectional+no_connect"))
    )
    (net (code "119") (name "unconnected-(U3C-IO_L45N_2-PadAB8)") (class "Default")
      (node (ref "U3") (pin "AB8") (pinfunction "IO_L45N_2_AB8") (pintype "bidirectional+no_connect"))
    )
    (net (code "120") (name "unconnected-(U3C-IO_L45P_2-PadAA8)") (class "Default")
      (node (ref "U3") (pin "AA8") (pinfunction "IO_L45P_2_AA8") (pintype "bidirectional+no_connect"))
    )
    (net (code "121") (name "unconnected-(U3C-IO_L46N_2-PadU10)") (class "Default")
      (node (ref "U3") (pin "U10") (pinfunction "IO_L46N_2_U10") (pintype "bidirectional+no_connect"))
    )
    (net (code "122") (name "unconnected-(U3C-IO_L46P_2-PadT10)") (class "Default")
      (node (ref "U3") (pin "T10") (pinfunction "IO_L46P_2_T10") (pintype "bidirectional+no_connect"))
    )
    (net (code "123") (name "unconnected-(U3C-IO_L47N_2-PadAB7)") (class "Default")
      (node (ref "U3") (pin "AB7") (pinfunction "IO_L47N_2_AB7") (pintype "bidirectional+no_connect"))
    )
    (net (code "124") (name "unconnected-(U3C-IO_L47P_2-PadY7)") (class "Default")
      (node (ref "U3") (pin "Y7") (pinfunction "IO_L47P_2_Y7") (pintype "bidirectional+no_connect"))
    )
    (net (code "125") (name "unconnected-(U3C-IO_L48N_RDWR_B_VREF_2-PadY8)") (class "Default")
      (node (ref "U3") (pin "Y8") (pinfunction "IO_L48N_RDWR_B_VREF_2_Y8") (pintype "bidirectional+no_connect"))
    )
    (net (code "126") (name "unconnected-(U3C-IO_L48P_D7_2-PadW9)") (class "Default")
      (node (ref "U3") (pin "W9") (pinfunction "IO_L48P_D7_2_W9") (pintype "bidirectional+no_connect"))
    )
    (net (code "127") (name "unconnected-(U3C-IO_L49N_D4_2-PadAB6)") (class "Default")
      (node (ref "U3") (pin "AB6") (pinfunction "IO_L49N_D4_2_AB6") (pintype "bidirectional+no_connect"))
    )
    (net (code "128") (name "unconnected-(U3C-IO_L49P_D3_2-PadAA6)") (class "Default")
      (node (ref "U3") (pin "AA6") (pinfunction "IO_L49P_D3_2_AA6") (pintype "bidirectional+no_connect"))
    )
    (net (code "129") (name "unconnected-(U3C-IO_L50N_2-PadV9)") (class "Default")
      (node (ref "U3") (pin "V9") (pinfunction "IO_L50N_2_V9") (pintype "bidirectional+no_connect"))
    )
    (net (code "130") (name "unconnected-(U3C-IO_L50P_2-PadU9)") (class "Default")
      (node (ref "U3") (pin "U9") (pinfunction "IO_L50P_2_U9") (pintype "bidirectional+no_connect"))
    )
    (net (code "131") (name "unconnected-(U3C-IO_L57N_2-PadU8)") (class "Default")
      (node (ref "U3") (pin "U8") (pinfunction "IO_L57N_2_U8") (pintype "bidirectional+no_connect"))
    )
    (net (code "132") (name "unconnected-(U3C-IO_L57P_2-PadT8)") (class "Default")
      (node (ref "U3") (pin "T8") (pinfunction "IO_L57P_2_T8") (pintype "bidirectional+no_connect"))
    )
    (net (code "133") (name "unconnected-(U3C-IO_L58N_2-PadW8)") (class "Default")
      (node (ref "U3") (pin "W8") (pinfunction "IO_L58N_2_W8") (pintype "bidirectional+no_connect"))
    )
    (net (code "134") (name "unconnected-(U3C-IO_L58P_2-PadV7)") (class "Default")
      (node (ref "U3") (pin "V7") (pinfunction "IO_L58P_2_V7") (pintype "bidirectional+no_connect"))
    )
    (net (code "135") (name "unconnected-(U3C-IO_L59N_2-PadR8)") (class "Default")
      (node (ref "U3") (pin "R8") (pinfunction "IO_L59N_2_R8") (pintype "bidirectional+no_connect"))
    )
    (net (code "136") (name "unconnected-(U3C-IO_L59P_2-PadR9)") (class "Default")
      (node (ref "U3") (pin "R9") (pinfunction "IO_L59P_2_R9") (pintype "bidirectional+no_connect"))
    )
    (net (code "137") (name "unconnected-(U3C-IO_L60N_2-PadY6)") (class "Default")
      (node (ref "U3") (pin "Y6") (pinfunction "IO_L60N_2_Y6") (pintype "bidirectional+no_connect"))
    )
    (net (code "138") (name "unconnected-(U3C-IO_L60P_2-PadW6)") (class "Default")
      (node (ref "U3") (pin "W6") (pinfunction "IO_L60P_2_W6") (pintype "bidirectional+no_connect"))
    )
  )
)
